# schematic.net
KiCad netlist of a schematic drawn in EAGLE
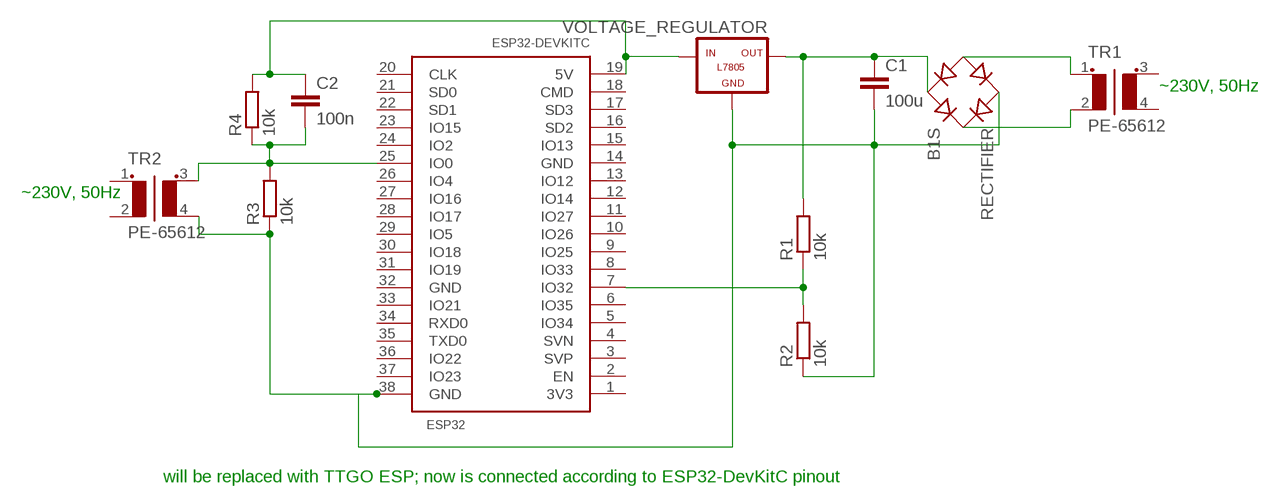
[diagram p0: schematic, sheet 1]

(export (version "E")
  (design (tool "Eeschema 10.0.6"))
  (components
    (comp (ref "C1")
      (value "100u")
      (footprint "eagle-import:C2.5-3")
      (libsource (lib "eagle-import") (part "C2,5-3"))
    )
    (comp (ref "C2")
      (value "100n")
      (footprint "eagle-import:C2.5-3")
      (libsource (lib "eagle-import") (part "C2,5-3"))
    )
    (comp (ref "ESP32")
      (value "ESP32DEVKITC")
      (footprint "eagle-import:ESP32-DEVKITC")
      (libsource (lib "eagle-import") (part "ESP32DEVKITC"))
    )
    (comp (ref "R1")
      (value "10k")
      (footprint "eagle-import:0204V")
      (libsource (lib "eagle-import") (part "R-EU_0204/2V"))
    )
    (comp (ref "R2")
      (value "10k")
      (footprint "eagle-import:0204V")
      (libsource (lib "eagle-import") (part "R-EU_0204/2V"))
    )
    (comp (ref "R3")
      (value "10k")
      (footprint "eagle-import:0204V")
      (libsource (lib "eagle-import") (part "R-EU_0204/2V"))
    )
    (comp (ref "R4")
      (value "10k")
      (footprint "eagle-import:0204V")
      (libsource (lib "eagle-import") (part "R-EU_0204/2V"))
    )
    (comp (ref "RECTIFIER")
      (value "B1S")
      (footprint "eagle-import:MBS")
      (libsource (lib "eagle-import") (part "BS1"))
    )
    (comp (ref "TR1")
      (value "PE-65612")
      (footprint "eagle-import:PE-65612")
      (libsource (lib "eagle-import") (part "PE-65612"))
    )
    (comp (ref "TR2")
      (value "PE-65612")
      (footprint "eagle-import:PE-65612")
      (libsource (lib "eagle-import") (part "PE-65612"))
    )
    (comp (ref "VOLTAGE_REGULATOR")
      (value "-L7805")
      (footprint "eagle-import:L7805")
      (libsource (lib "eagle-import") (part "-L7805"))
    )
  )
  (nets
    (net (code "1") (name "Net-(C1-Pad1)") (class "Default")
      (node (ref "C1") (pin "1") (pinfunction "1_1") (pintype "passive"))
      (node (ref "R1") (pin "2") (pinfunction "2_2") (pintype "passive"))
      (node (ref "RECTIFIER") (pin "AC2") (pinfunction "AC2_AC2") (pintype "passive"))
      (node (ref "VOLTAGE_REGULATOR") (pin "OUT") (pinfunction "OUT_OUT") (pintype "passive"))
    )
    (net (code "2") (name "Net-(ESP32-5V)") (class "Default")
      (node (ref "C2") (pin "1") (pinfunction "1_1") (pintype "passive"))
      (node (ref "ESP32") (pin "19") (pinfunction "5V_19") (pintype "bidirectional"))
      (node (ref "R4") (pin "2") (pinfunction "2_2") (pintype "passive"))
      (node (ref "VOLTAGE_REGULATOR") (pin "IN") (pinfunction "IN_IN") (pintype "input"))
    )
    (net (code "3") (name "Net-(ESP32-IO0)") (class "Default")
      (node (ref "C2") (pin "2") (pinfunction "2_2") (pintype "passive"))
      (node (ref "ESP32") (pin "25") (pinfunction "IO0_25") (pintype "bidirectional"))
      (node (ref "R3") (pin "2") (pinfunction "2_2") (pintype "passive"))
      (node (ref "R4") (pin "1") (pinfunction "1_1") (pintype "passive"))
      (node (ref "TR2") (pin "3") (pinfunction "S1_3") (pintype "passive"))
    )
    (net (code "4") (name "Net-(ESP32-IO32)") (class "Default")
      (node (ref "ESP32") (pin "7") (pinfunction "IO32_7") (pintype "bidirectional"))
      (node (ref "R1") (pin "1") (pinfunction "1_1") (pintype "passive"))
      (node (ref "R2") (pin "2") (pinfunction "2_2") (pintype "passive"))
    )
    (net (code "5") (name "Net-(TR1-P1)") (class "Default")
      (node (ref "RECTIFIER") (pin "-") (pinfunction "-_-") (pintype "passive"))
      (node (ref "TR1") (pin "1") (pinfunction "P1_1") (pintype "passive"))
    )
    (net (code "6") (name "Net-(TR1-P2)") (class "Default")
      (node (ref "RECTIFIER") (pin "+") (pinfunction "+_+") (pintype "passive"))
      (node (ref "TR1") (pin "2") (pinfunction "P2_2") (pintype "passive"))
    )
    (net (code "7") (name "Net-(TR2-S2)") (class "Default")
      (node (ref "C1") (pin "2") (pinfunction "2_2") (pintype "passive"))
      (node (ref "ESP32") (pin "38") (pinfunction "GND_38") (pintype "bidirectional"))
      (node (ref "R2") (pin "1") (pinfunction "1_1") (pintype "passive"))
      (node (ref "R3") (pin "1") (pinfunction "1_1") (pintype "passive"))
      (node (ref "RECTIFIER") (pin "AC1") (pinfunction "AC1_AC1") (pintype "passive"))
      (node (ref "TR2") (pin "4") (pinfunction "S2_4") (pintype "passive"))
      (node (ref "VOLTAGE_REGULATOR") (pin "GND") (pinfunction "GND_GND") (pintype "input"))
    )
    (net (code "8") (name "unconnected-(ESP32-3V3-Pad1)") (class "Default")
      (node (ref "ESP32") (pin "1") (pinfunction "3V3_1") (pintype "bidirectional"))
    )
    (net (code "9") (name "unconnected-(ESP32-CLK-Pad20)") (class "Default")
      (node (ref "ESP32") (pin "20") (pinfunction "CLK_20") (pintype "bidirectional"))
    )
    (net (code "10") (name "unconnected-(ESP32-CMD-Pad18)") (class "Default")
      (node (ref "ESP32") (pin "18") (pinfunction "CMD_18") (pintype "bidirectional"))
    )
    (net (code "11") (name "unconnected-(ESP32-EN-Pad2)") (class "Default")
      (node (ref "ESP32") (pin "2") (pinfunction "EN_2") (pintype "bidirectional"))
    )
    (net (code "12") (name "unconnected-(ESP32-GND-Pad14)") (class "Default")
      (node (ref "ESP32") (pin "14") (pinfunction "GND_14") (pintype "bidirectional"))
    )
    (net (code "13") (name "unconnected-(ESP32-GND-Pad32)") (class "Default")
      (node (ref "ESP32") (pin "32") (pinfunction "GND_32") (pintype "bidirectional"))
    )
    (net (code "14") (name "unconnected-(ESP32-IO2-Pad24)") (class "Default")
      (node (ref "ESP32") (pin "24") (pinfunction "IO2_24") (pintype "bidirectional"))
    )
    (net (code "15") (name "unconnected-(ESP32-IO4-Pad26)") (class "Default")
      (node (ref "ESP32") (pin "26") (pinfunction "IO4_26") (pintype "bidirectional"))
    )
    (net (code "16") (name "unconnected-(ESP32-IO5-Pad29)") (class "Default")
      (node (ref "ESP32") (pin "29") (pinfunction "IO5_29") (pintype "bidirectional"))
    )
    (net (code "17") (name "unconnected-(ESP32-IO12-Pad13)") (class "Default")
      (node (ref "ESP32") (pin "13") (pinfunction "IO12_13") (pintype "bidirectional"))
    )
    (net (code "18") (name "unconnected-(ESP32-IO13-Pad15)") (class "Default")
      (node (ref "ESP32") (pin "15") (pinfunction "IO13_15") (pintype "bidirectional"))
    )
    (net (code "19") (name "unconnected-(ESP32-IO14-Pad12)") (class "Default")
      (node (ref "ESP32") (pin "12") (pinfunction "IO14_12") (pintype "bidirectional"))
    )
    (net (code "20") (name "unconnected-(ESP32-IO15-Pad23)") (class "Default")
      (node (ref "ESP32") (pin "23") (pinfunction "IO15_23") (pintype "bidirectional"))
    )
    (net (code "21") (name "unconnected-(ESP32-IO16-Pad27)") (class "Default")
      (node (ref "ESP32") (pin "27") (pinfunction "IO16_27") (pintype "bidirectional"))
    )
    (net (code "22") (name "unconnected-(ESP32-IO17-Pad28)") (class "Default")
      (node (ref "ESP32") (pin "28") (pinfunction "IO17_28") (pintype "bidirectional"))
    )
    (net (code "23") (name "unconnected-(ESP32-IO18-Pad30)") (class "Default")
      (node (ref "ESP32") (pin "30") (pinfunction "IO18_30") (pintype "bidirectional"))
    )
    (net (code "24") (name "unconnected-(ESP32-IO19-Pad31)") (class "Default")
      (node (ref "ESP32") (pin "31") (pinfunction "IO19_31") (pintype "bidirectional"))
    )
    (net (code "25") (name "unconnected-(ESP32-IO21-Pad33)") (class "Default")
      (node (ref "ESP32") (pin "33") (pinfunction "IO21_33") (pintype "bidirectional"))
    )
    (net (code "26") (name "unconnected-(ESP32-IO22-Pad36)") (class "Default")
      (node (ref "ESP32") (pin "36") (pinfunction "IO22_36") (pintype "bidirectional"))
    )
    (net (code "27") (name "unconnected-(ESP32-IO23-Pad37)") (class "Default")
      (node (ref "ESP32") (pin "37") (pinfunction "IO23_37") (pintype "bidirectional"))
    )
    (net (code "28") (name "unconnected-(ESP32-IO25-Pad9)") (class "Default")
      (node (ref "ESP32") (pin "9") (pinfunction "IO25_9") (pintype "bidirectional"))
    )
    (net (code "29") (name "unconnected-(ESP32-IO26-Pad10)") (class "Default")
      (node (ref "ESP32") (pin "10") (pinfunction "IO26_10") (pintype "bidirectional"))
    )
    (net (code "30") (name "unconnected-(ESP32-IO27-Pad11)") (class "Default")
      (node (ref "ESP32") (pin "11") (pinfunction "IO27_11") (pintype "bidirectional"))
    )
    (net (code "31") (name "unconnected-(ESP32-IO33-Pad8)") (class "Default")
      (node (ref "ESP32") (pin "8") (pinfunction "IO33_8") (pintype "bidirectional"))
    )
    (net (code "32") (name "unconnected-(ESP32-IO34-Pad5)") (class "Default")
      (node (ref "ESP32") (pin "5") (pinfunction "IO34_5") (pintype "bidirectional"))
    )
    (net (code "33") (name "unconnected-(ESP32-IO35-Pad6)") (class "Default")
      (node (ref "ESP32") (pin "6") (pinfunction "IO35_6") (pintype "bidirectional"))
    )
    (net (code "34") (name "unconnected-(ESP32-RXD0-Pad34)") (class "Default")
      (node (ref "ESP32") (pin "34") (pinfunction "RXD0_34") (pintype "bidirectional"))
    )
    (net (code "35") (name "unconnected-(ESP32-SD0-Pad21)") (class "Default")
      (node (ref "ESP32") (pin "21") (pinfunction "SD0_21") (pintype "bidirectional"))
    )
    (net (code "36") (name "unconnected-(ESP32-SD1-Pad22)") (class "Default")
      (node (ref "ESP32") (pin "22") (pinfunction "SD1_22") (pintype "bidirectional"))
    )
    (net (code "37") (name "unconnected-(ESP32-SD2-Pad16)") (class "Default")
      (node (ref "ESP32") (pin "16") (pinfunction "SD2_16") (pintype "bidirectional"))
    )
    (net (code "38") (name "unconnected-(ESP32-SD3-Pad17)") (class "Default")
      (node (ref "ESP32") (pin "17") (pinfunction "SD3_17") (pintype "bidirectional"))
    )
    (net (code "39") (name "unconnected-(ESP32-SVN-Pad4)") (class "Default")
      (node (ref "ESP32") (pin "4") (pinfunction "SVN_4") (pintype "bidirectional"))
    )
    (net (code "40") (name "unconnected-(ESP32-SVP-Pad3)") (class "Default")
      (node (ref "ESP32") (pin "3") (pinfunction "SVP_3") (pintype "bidirectional"))
    )
    (net (code "41") (name "unconnected-(ESP32-TXD0-Pad35)") (class "Default")
      (node (ref "ESP32") (pin "35") (pinfunction "TXD0_35") (pintype "bidirectional"))
    )
    (net (code "42") (name "unconnected-(TR1-S1-Pad3)") (class "Default")
      (node (ref "TR1") (pin "3") (pinfunction "S1_3") (pintype "passive"))
    )
    (net (code "43") (name "unconnected-(TR1-S2-Pad4)") (class "Default")
      (node (ref "TR1") (pin "4") (pinfunction "S2_4") (pintype "passive"))
    )
    (net (code "44") (name "unconnected-(TR2-P1-Pad1)") (class "Default")
      (node (ref "TR2") (pin "1") (pinfunction "P1_1") (pintype "passive"))
    )
    (net (code "45") (name "unconnected-(TR2-P2-Pad2)") (class "Default")
      (node (ref "TR2") (pin "2") (pinfunction "P2_2") (pintype "passive"))
    )
  )
)
